# PowerSwitch.net
KiCad netlist of a schematic drawn in Altium Designer
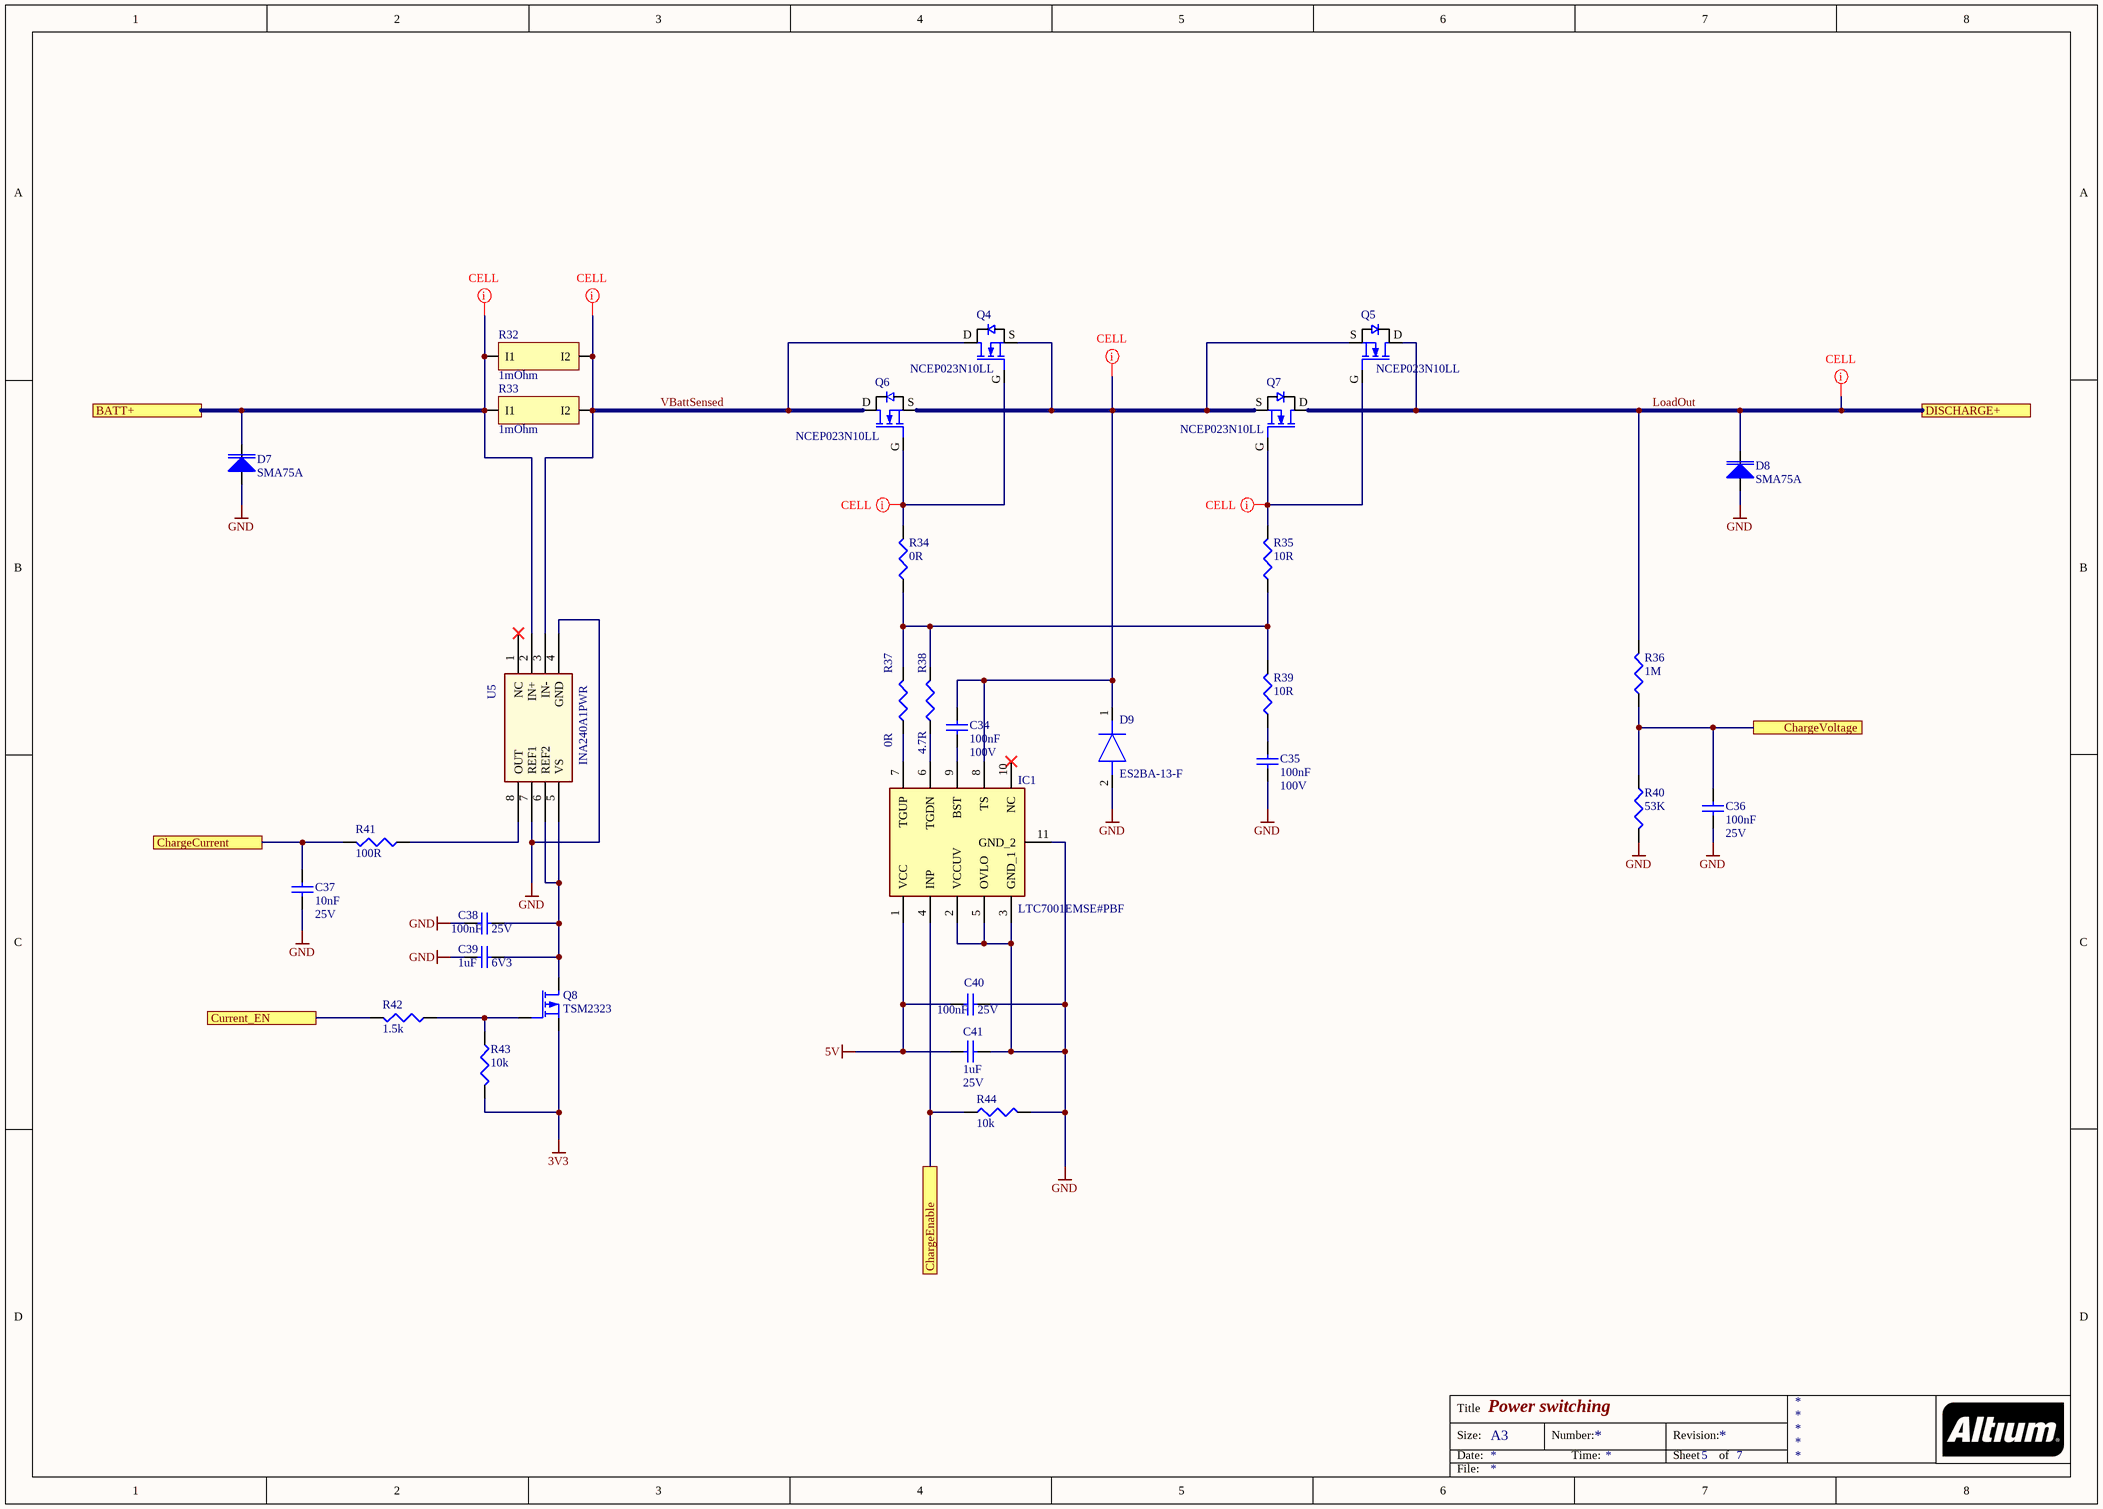
[diagram p0: PowerSwitch.SchDoc]

(export (version "E")
  (design (tool "Eeschema 10.0.6"))
  (components
    (comp (ref "C34")
      (value "100nF")
      (footprint "VESC_BMS:C-1206")
      (description "Capacitor, 1uF, 100V, X7R")
      (fields (field (name "VOLTAGE RATING") "100V"))
      (libsource (lib "AR_Capacitors_Ceramic") (part "1uF/1206/CER/100V"))
    )
    (comp (ref "C35")
      (value "100nF")
      (footprint "VESC_BMS:C-1206")
      (description "Capacitor, 1uF, 100V, X7R")
      (fields (field (name "VOLTAGE RATING") "100V"))
      (libsource (lib "AR_Capacitors_Ceramic") (part "1uF/1206/CER/100V"))
    )
    (comp (ref "C36")
      (value "100nF")
      (footprint "VESC_BMS:C0402")
      (description "Capacitor, 100nF, 25V, X7R")
      (fields (field (name "VOLTAGE RATING") "25V"))
      (libsource (lib "AR_Capacitors_Ceramic") (part "100nF/0402/CER/25V"))
    )
    (comp (ref "C37")
      (value "10nF")
      (footprint "VESC_BMS:C0402")
      (description "Capacitor, 100nF, 25V, X7R")
      (fields (field (name "VOLTAGE RATING") "25V"))
      (libsource (lib "AR_Capacitors_Ceramic") (part "100nF/0402/CER/25V"))
    )
    (comp (ref "C38")
      (value "100nF")
      (footprint "VESC_BMS:C0402")
      (description "Capacitor, 100nF, 25V, X7R")
      (fields (field (name "VOLTAGE RATING") "25V"))
      (libsource (lib "AR_Capacitors_Ceramic") (part "100nF/0402/CER/25V"))
    )
    (comp (ref "C39")
      (value "1uF")
      (footprint "VESC_BMS:C0402")
      (description "Capacitor, 1uF, 6.3V, X5R")
      (fields (field (name "VOLTAGE RATING") "6V3"))
      (libsource (lib "AR_Capacitors_Ceramic") (part "1uF/0402/CER/6.3V"))
    )
    (comp (ref "C40")
      (value "100nF")
      (footprint "VESC_BMS:C0402")
      (description "Capacitor, 100nF, 25V, X7R")
      (fields (field (name "VOLTAGE RATING") "25V"))
      (libsource (lib "AR_Capacitors_Ceramic") (part "100nF/0402/CER/25V"))
    )
    (comp (ref "C41")
      (value "1uF")
      (footprint "VESC_BMS:C0402")
      (description "Capacitor, 100nF, 25V, X7R")
      (fields (field (name "VOLTAGE RATING") "25V"))
      (libsource (lib "AR_Capacitors_Ceramic") (part "100nF/0402/CER/25V"))
    )
    (comp (ref "D7")
      (value "SMA75A")
      (footprint "DIOM7959X262N")
      (description "Diode TVS, Vrwm: 75V, Vbr: 81.9V, Vc: 113V, Ippm: 27A")
      (libsource (lib "VESC_BMS") (part "SMA75A"))
    )
    (comp (ref "D8")
      (value "SMA75A")
      (footprint "DIOM7959X262N")
      (description "Diode TVS, Vrwm: 75V, Vbr: 81.9V, Vc: 113V, Ippm: 27A")
      (libsource (lib "VESC_BMS") (part "SMA75A"))
    )
    (comp (ref "D9")
      (value "ES2BA-13-F")
      (footprint "DIOM5226X230N")
      (description "Diode")
      (fields (field (name "MOUSER PART NUMBER") "621-ES2BA-F"))
      (libsource (lib "VESC_BMS") (part "ES2BA-13-F"))
    )
    (comp (ref "IC1")
      (value "LTC7001EMSE#PBF")
      (footprint "VESC_BMS:SOP50P490X110-11N")
      (description "Integrated Circuit")
      (fields (field (name "MOUSER PART NUMBER") "584-LTC7001EMSEPBF"))
      (libsource (lib "VESC_BMS") (part "LTC7001EMSE#PBF"))
    )
    (comp (ref "Q4")
      (value "NCEP023N10LL")
      (footprint "VESC_BMS:TOLL")
      (description "Mosfet, N-channel, Vds:100V, Id:330A, Vgs-th:3.7V, Rds-on:0.00115ohm")
      (libsource (lib "VESC_BMS") (part "NCEP023N10LL"))
    )
    (comp (ref "Q5")
      (value "NCEP023N10LL")
      (footprint "VESC_BMS:TOLL")
      (description "Mosfet, N-channel, Vds:100V, Id:330A, Vgs-th:3.7V, Rds-on:0.00115ohm")
      (libsource (lib "VESC_BMS") (part "NCEP023N10LL"))
    )
    (comp (ref "Q6")
      (value "NCEP023N10LL")
      (footprint "VESC_BMS:TOLL")
      (description "Mosfet, N-channel, Vds:100V, Id:330A, Vgs-th:3.7V, Rds-on:0.00115ohm")
      (libsource (lib "VESC_BMS") (part "NCEP023N10LL"))
    )
    (comp (ref "Q7")
      (value "NCEP023N10LL")
      (footprint "VESC_BMS:TOLL")
      (description "Mosfet, N-channel, Vds:100V, Id:330A, Vgs-th:3.7V, Rds-on:0.00115ohm")
      (libsource (lib "VESC_BMS") (part "NCEP023N10LL"))
    )
    (comp (ref "Q8")
      (value "TSM2323")
      (footprint "VESC_BMS:SOT-23")
      (description "Mosfet, P-channel, Vds:20V, Id:4.7A, Vgs-th:1V, Rds-on:0.039ohm")
      (libsource (lib "AR_Mosfets") (part "TSM2323"))
    )
    (comp (ref "R32")
      (value "1mOhm")
      (footprint "VESC_BMS:RES-SMD_L10.0-W5.2")
      (description "1mohm, 5 W, ± 5%, 4320 Wide")
      (libsource (lib "AR_Misc") (part "FCSL110R001JER"))
    )
    (comp (ref "R33")
      (value "1mOhm")
      (footprint "VESC_BMS:RES-SMD_L10.0-W5.2")
      (description "1mohm, 5 W, ± 5%, 4320 Wide")
      (libsource (lib "AR_Misc") (part "FCSL110R001JER"))
    )
    (comp (ref "R34")
      (value "0R")
      (footprint "VESC_BMS:0603")
      (description "Resistor, 100R, 1%, 0.063W, 50V, 200PPM, 0603")
      (libsource (lib "AR_Resistors_SMD") (part "100/0603/0063W/50V"))
    )
    (comp (ref "R35")
      (value "10R")
      (footprint "VESC_BMS:0603")
      (description "Resistor, 100R, 1%, 0.063W, 50V, 200PPM, 0603")
      (libsource (lib "AR_Resistors_SMD") (part "100/0603/0063W/50V"))
    )
    (comp (ref "R36")
      (value "1M")
      (footprint "VESC_BMS:0402")
      (description "Resistor, 1.5k, 0.1%, 0.0625W, 50V, 100PPM, 0402")
      (libsource (lib "AR_Resistors_SMD") (part "1.5k/0402/0063W/50V"))
    )
    (comp (ref "R37")
      (value "0R")
      (footprint "VESC_BMS:0603")
      (description "Resistor, 100R, 1%, 0.063W, 50V, 200PPM, 0603")
      (libsource (lib "AR_Resistors_SMD") (part "100/0603/0063W/50V"))
    )
    (comp (ref "R38")
      (value "4.7R")
      (footprint "VESC_BMS:0603")
      (description "Resistor, 100R, 1%, 0.063W, 50V, 200PPM, 0603")
      (libsource (lib "AR_Resistors_SMD") (part "100/0603/0063W/50V"))
    )
    (comp (ref "R39")
      (value "10R")
      (footprint "VESC_BMS:0603")
      (description "Resistor, 100R, 1%, 0.063W, 50V, 200PPM, 0603")
      (libsource (lib "AR_Resistors_SMD") (part "100/0603/0063W/50V"))
    )
    (comp (ref "R40")
      (value "53K")
      (footprint "VESC_BMS:0402")
      (description "Resistor, 1.5k, 0.1%, 0.0625W, 50V, 100PPM, 0402")
      (libsource (lib "AR_Resistors_SMD") (part "1.5k/0402/0063W/50V"))
    )
    (comp (ref "R41")
      (value "100R")
      (footprint "VESC_BMS:0402")
      (description "Resistor, 1.5k, 0.1%, 0.0625W, 50V, 100PPM, 0402")
      (libsource (lib "AR_Resistors_SMD") (part "1.5k/0402/0063W/50V"))
    )
    (comp (ref "R42")
      (value "1.5k")
      (footprint "VESC_BMS:0402")
      (description "Resistor, 1.5k, 0.1%, 0.0625W, 50V, 100PPM, 0402")
      (libsource (lib "AR_Resistors_SMD") (part "1.5k/0402/0063W/50V"))
    )
    (comp (ref "R43")
      (value "10k")
      (footprint "VESC_BMS:0402")
      (description "Resistor, 1.5k, 0.1%, 0.0625W, 50V, 100PPM, 0402")
      (libsource (lib "AR_Resistors_SMD") (part "1.5k/0402/0063W/50V"))
    )
    (comp (ref "R44")
      (value "10k")
      (footprint "VESC_BMS:0402")
      (description "Resistor, 1.5k, 0.1%, 0.0625W, 50V, 100PPM, 0402")
      (libsource (lib "AR_Resistors_SMD") (part "1.5k/0402/0063W/50V"))
    )
    (comp (ref "U5")
      (value "INA240A1PWR")
      (footprint "VESC_BMS:TSSOP-8")
      (libsource (lib "DB10005_DieBieMS") (part "INA240A1PWR"))
    )
  )
  (nets
    (net (code "1") (name "/BATT+") (class "Default")
      (node (ref "D7") (pin "2") (pinfunction "2_2") (pintype "passive"))
      (node (ref "R32") (pin "0") (pinfunction "I1_0") (pintype "passive"))
      (node (ref "R33") (pin "0") (pinfunction "I1_0") (pintype "passive"))
      (node (ref "U5") (pin "2") (pinfunction "IN+_2") (pintype "passive"))
    )
    (net (code "2") (name "/ChargeCurrent") (class "Default")
      (node (ref "C37") (pin "2") (pinfunction "2_2") (pintype "passive"))
      (node (ref "R41") (pin "2") (pinfunction "2_2") (pintype "passive"))
    )
    (net (code "3") (name "/ChargeEnable") (class "Default")
      (node (ref "IC1") (pin "4") (pinfunction "INP_4") (pintype "passive"))
      (node (ref "R44") (pin "1") (pinfunction "1_1") (pintype "passive"))
    )
    (net (code "4") (name "/ChargeVoltage") (class "Default")
      (node (ref "C36") (pin "2") (pinfunction "2_2") (pintype "passive"))
      (node (ref "R36") (pin "1") (pinfunction "1_1") (pintype "passive"))
      (node (ref "R40") (pin "1") (pinfunction "1_1") (pintype "passive"))
    )
    (net (code "5") (name "/Current_EN") (class "Default")
      (node (ref "R42") (pin "2") (pinfunction "2_2") (pintype "passive"))
    )
    (net (code "6") (name "/LoadOut") (class "Default")
      (node (ref "D8") (pin "2") (pinfunction "2_2") (pintype "passive"))
      (node (ref "Q5") (pin "D") (pinfunction "D_D") (pintype "passive"))
      (node (ref "Q7") (pin "D") (pinfunction "D_D") (pintype "passive"))
      (node (ref "R36") (pin "2") (pinfunction "2_2") (pintype "passive"))
    )
    (net (code "7") (name "/VBattSensed") (class "Default")
      (node (ref "Q4") (pin "D") (pinfunction "D_D") (pintype "passive"))
      (node (ref "Q6") (pin "D") (pinfunction "D_D") (pintype "passive"))
      (node (ref "R32") (pin "1") (pinfunction "I2_1") (pintype "passive"))
      (node (ref "R33") (pin "1") (pinfunction "I2_1") (pintype "passive"))
      (node (ref "U5") (pin "3") (pinfunction "IN-_3") (pintype "passive"))
    )
    (net (code "8") (name "3V3") (class "Default")
      (node (ref "Q8") (pin "S") (pinfunction "S_S") (pintype "passive"))
      (node (ref "R43") (pin "2") (pinfunction "2_2") (pintype "passive"))
    )
    (net (code "9") (name "5V") (class "Default")
      (node (ref "C40") (pin "1") (pinfunction "1_1") (pintype "passive"))
      (node (ref "C41") (pin "2") (pinfunction "2_2") (pintype "passive"))
      (node (ref "IC1") (pin "1") (pinfunction "VCC_1") (pintype "passive"))
    )
    (net (code "10") (name "GND") (class "Default")
      (node (ref "C35") (pin "1") (pinfunction "1_1") (pintype "passive"))
      (node (ref "C36") (pin "1") (pinfunction "1_1") (pintype "passive"))
      (node (ref "C37") (pin "1") (pinfunction "1_1") (pintype "passive"))
      (node (ref "C38") (pin "1") (pinfunction "1_1") (pintype "passive"))
      (node (ref "C39") (pin "1") (pinfunction "1_1") (pintype "passive"))
      (node (ref "C40") (pin "2") (pinfunction "2_2") (pintype "passive"))
      (node (ref "C41") (pin "1") (pinfunction "1_1") (pintype "passive"))
      (node (ref "D7") (pin "1") (pinfunction "1_1") (pintype "passive"))
      (node (ref "D8") (pin "1") (pinfunction "1_1") (pintype "passive"))
      (node (ref "D9") (pin "2") (pinfunction "A_2") (pintype "passive"))
      (node (ref "IC1") (pin "11") (pinfunction "GND_2_11") (pintype "passive"))
      (node (ref "IC1") (pin "2") (pinfunction "VCCUV_2") (pintype "passive"))
      (node (ref "IC1") (pin "3") (pinfunction "GND_1_3") (pintype "passive"))
      (node (ref "IC1") (pin "5") (pinfunction "OVLO_5") (pintype "passive"))
      (node (ref "R40") (pin "2") (pinfunction "2_2") (pintype "passive"))
      (node (ref "R44") (pin "2") (pinfunction "2_2") (pintype "passive"))
      (node (ref "U5") (pin "4") (pinfunction "GND_4") (pintype "passive"))
      (node (ref "U5") (pin "7") (pinfunction "REF1_7") (pintype "passive"))
    )
    (net (code "11") (name "Net-(C35-Pad2)") (class "Default")
      (node (ref "C35") (pin "2") (pinfunction "2_2") (pintype "passive"))
      (node (ref "R39") (pin "1") (pinfunction "1_1") (pintype "passive"))
    )
    (net (code "12") (name "Net-(D9-K)") (class "Default")
      (node (ref "C34") (pin "2") (pinfunction "2_2") (pintype "passive"))
      (node (ref "D9") (pin "1") (pinfunction "K_1") (pintype "passive"))
      (node (ref "IC1") (pin "8") (pinfunction "TS_8") (pintype "passive"))
      (node (ref "Q4") (pin "S") (pinfunction "S_S") (pintype "passive"))
      (node (ref "Q5") (pin "S") (pinfunction "S_S") (pintype "passive"))
      (node (ref "Q6") (pin "S") (pinfunction "S_S") (pintype "passive"))
      (node (ref "Q7") (pin "S") (pinfunction "S_S") (pintype "passive"))
    )
    (net (code "13") (name "Net-(IC1-BST)") (class "Default")
      (node (ref "C34") (pin "1") (pinfunction "1_1") (pintype "passive"))
      (node (ref "IC1") (pin "9") (pinfunction "BST_9") (pintype "passive"))
    )
    (net (code "14") (name "Net-(IC1-TGDN)") (class "Default")
      (node (ref "IC1") (pin "6") (pinfunction "TGDN_6") (pintype "passive"))
      (node (ref "R38") (pin "1") (pinfunction "1_1") (pintype "passive"))
    )
    (net (code "15") (name "Net-(IC1-TGUP)") (class "Default")
      (node (ref "IC1") (pin "7") (pinfunction "TGUP_7") (pintype "passive"))
      (node (ref "R37") (pin "1") (pinfunction "1_1") (pintype "passive"))
    )
    (net (code "16") (name "Net-(Q4-PadG)") (class "Default")
      (node (ref "Q4") (pin "G") (pinfunction "G_G") (pintype "passive"))
      (node (ref "Q6") (pin "G") (pinfunction "G_G") (pintype "passive"))
      (node (ref "R34") (pin "2") (pinfunction "2_2") (pintype "passive"))
    )
    (net (code "17") (name "Net-(Q5-PadG)") (class "Default")
      (node (ref "Q5") (pin "G") (pinfunction "G_G") (pintype "passive"))
      (node (ref "Q7") (pin "G") (pinfunction "G_G") (pintype "passive"))
      (node (ref "R35") (pin "2") (pinfunction "2_2") (pintype "passive"))
    )
    (net (code "18") (name "Net-(Q8-PadG)") (class "Default")
      (node (ref "Q8") (pin "G") (pinfunction "G_G") (pintype "passive"))
      (node (ref "R42") (pin "1") (pinfunction "1_1") (pintype "passive"))
      (node (ref "R43") (pin "1") (pinfunction "1_1") (pintype "passive"))
    )
    (net (code "19") (name "Net-(R34-Pad1)") (class "Default")
      (node (ref "R34") (pin "1") (pinfunction "1_1") (pintype "passive"))
      (node (ref "R35") (pin "1") (pinfunction "1_1") (pintype "passive"))
      (node (ref "R37") (pin "2") (pinfunction "2_2") (pintype "passive"))
      (node (ref "R38") (pin "2") (pinfunction "2_2") (pintype "passive"))
      (node (ref "R39") (pin "2") (pinfunction "2_2") (pintype "passive"))
    )
    (net (code "20") (name "Net-(U5-OUT)") (class "Default")
      (node (ref "R41") (pin "1") (pinfunction "1_1") (pintype "passive"))
      (node (ref "U5") (pin "8") (pinfunction "OUT_8") (pintype "passive"))
    )
    (net (code "21") (name "Net-(U5-REF2)") (class "Default")
      (node (ref "C38") (pin "2") (pinfunction "2_2") (pintype "passive"))
      (node (ref "C39") (pin "2") (pinfunction "2_2") (pintype "passive"))
      (node (ref "Q8") (pin "D") (pinfunction "D_D") (pintype "passive"))
      (node (ref "U5") (pin "5") (pinfunction "VS_5") (pintype "passive"))
      (node (ref "U5") (pin "6") (pinfunction "REF2_6") (pintype "passive"))
    )
    (net (code "22") (name "unconnected-(IC1-NC-Pad10)") (class "Default")
      (node (ref "IC1") (pin "10") (pinfunction "NC_10") (pintype "passive+no_connect"))
    )
    (net (code "23") (name "unconnected-(U5-NC-Pad1)") (class "Default")
      (node (ref "U5") (pin "1") (pinfunction "NC_1") (pintype "passive+no_connect"))
    )
  )
)
